# RF_old.net
KiCad netlist of a schematic drawn in Altium Designer
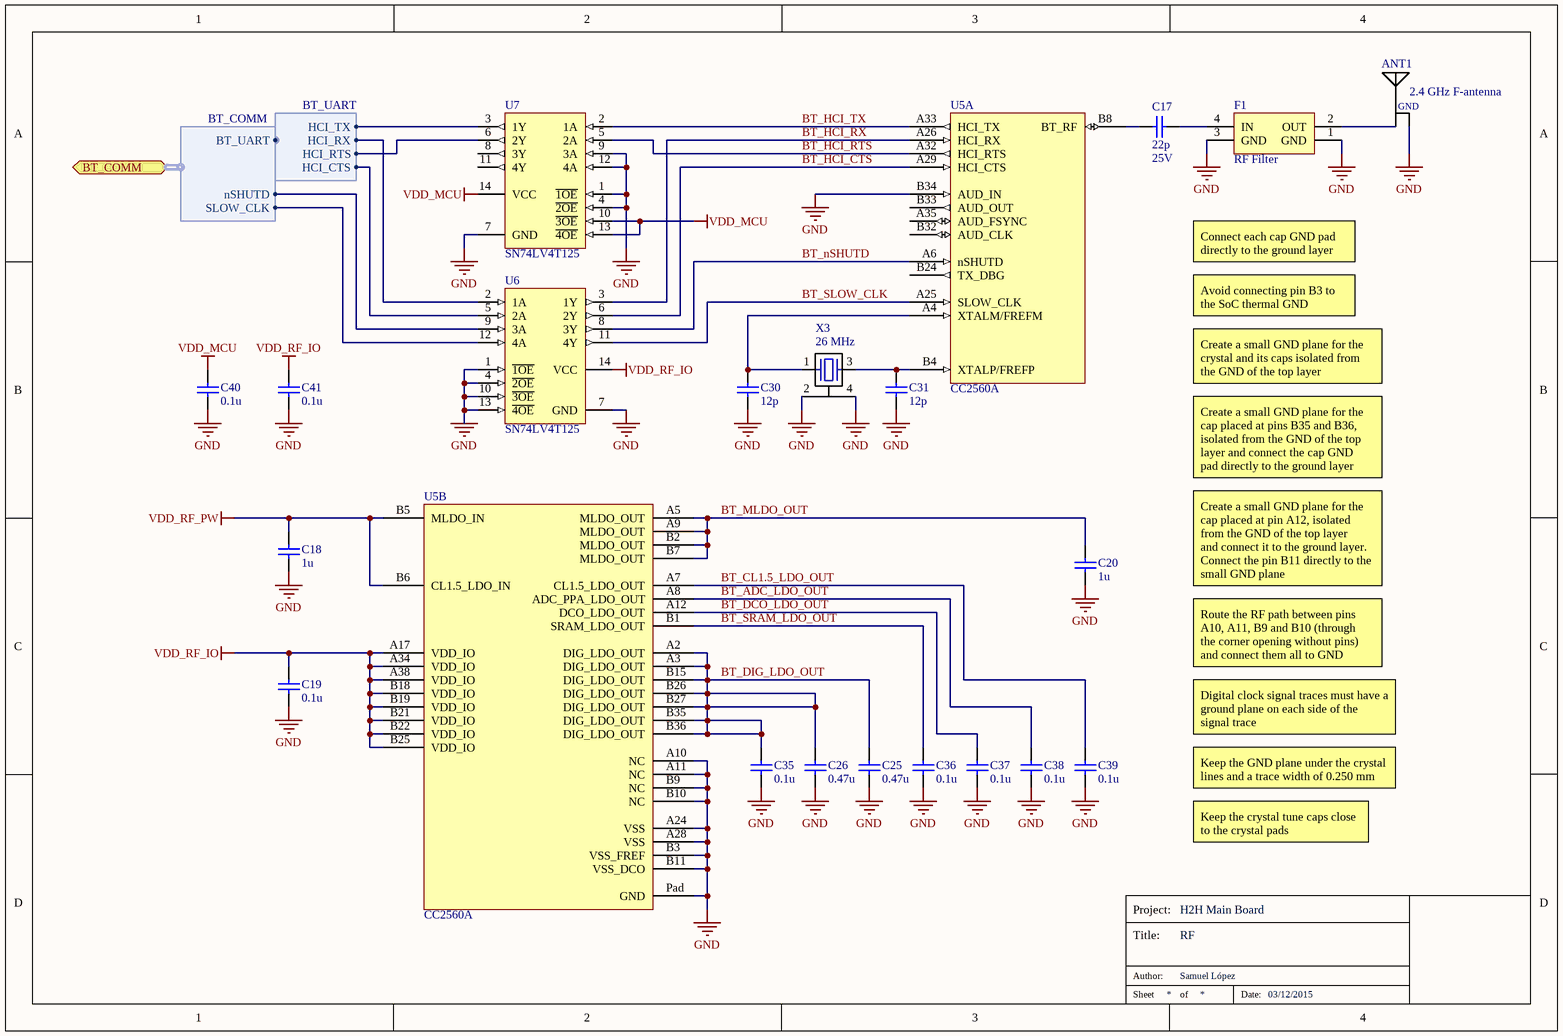
[diagram p0: RF_old.SchDoc]

(export (version "E")
  (design (tool "Eeschema 10.0.6"))
  (components
    (comp (ref "ANT1")
      (value "2.4 GHz F-antenna")
      (footprint "Antenna")
      (libsource (lib "Main Board") (part "Antenna"))
    )
    (comp (ref "C17")
      (value "22p")
      (footprint "C0603")
      (description "Capacitor")
      (fields (field (name "RATED VOLTAGE") "25V"))
      (libsource (lib "Common Devices") (part "Capacitor"))
    )
    (comp (ref "C18")
      (value "1u")
      (footprint "C0603")
      (description "Capacitor")
      (libsource (lib "Common Devices") (part "Capacitor"))
    )
    (comp (ref "C19")
      (value "0.1u")
      (footprint "C0603")
      (description "Capacitor")
      (libsource (lib "Common Devices") (part "Capacitor"))
    )
    (comp (ref "C20")
      (value "1u")
      (footprint "C0603")
      (description "Capacitor")
      (libsource (lib "Common Devices") (part "Capacitor"))
    )
    (comp (ref "C25")
      (value "0.47u")
      (footprint "C0603")
      (description "Capacitor")
      (libsource (lib "Common Devices") (part "Capacitor"))
    )
    (comp (ref "C26")
      (value "0.47u")
      (footprint "C0603")
      (description "Capacitor")
      (libsource (lib "Common Devices") (part "Capacitor"))
    )
    (comp (ref "C30")
      (value "12p")
      (footprint "C0603")
      (description "Capacitor")
      (libsource (lib "Common Devices") (part "Capacitor"))
    )
    (comp (ref "C31")
      (value "12p")
      (footprint "C0603")
      (description "Capacitor")
      (libsource (lib "Common Devices") (part "Capacitor"))
    )
    (comp (ref "C35")
      (value "0.1u")
      (footprint "C0603")
      (description "Capacitor")
      (libsource (lib "Common Devices") (part "Capacitor"))
    )
    (comp (ref "C36")
      (value "0.1u")
      (footprint "C0603")
      (description "Capacitor")
      (libsource (lib "Common Devices") (part "Capacitor"))
    )
    (comp (ref "C37")
      (value "0.1u")
      (footprint "C0603")
      (description "Capacitor")
      (libsource (lib "Common Devices") (part "Capacitor"))
    )
    (comp (ref "C38")
      (value "0.1u")
      (footprint "C0603")
      (description "Capacitor")
      (libsource (lib "Common Devices") (part "Capacitor"))
    )
    (comp (ref "C39")
      (value "0.1u")
      (footprint "C0603")
      (description "Capacitor")
      (libsource (lib "Common Devices") (part "Capacitor"))
    )
    (comp (ref "C40")
      (value "0.1u")
      (footprint "C0603")
      (description "Capacitor")
      (libsource (lib "Common Devices") (part "Capacitor"))
    )
    (comp (ref "C41")
      (value "0.1u")
      (footprint "C0603")
      (description "Capacitor")
      (libsource (lib "Common Devices") (part "Capacitor"))
    )
    (comp (ref "F1")
      (value "RF Filter")
      (footprint "LFB212G45SG8A127")
      (description "RF Filter 2.4 GHz")
      (libsource (lib "Main Board") (part "LFB212G45SG8A127"))
    )
    (comp (ref "U5")
      (value "CC2560A")
      (footprint "CC2560")
      (description "Bluetooth - BT 4.0 controller (BR/EDR)")
      (libsource (lib "Main Board") (part "CC2560A"))
    )
    (comp (ref "U6")
      (value "SN74LV4T125")
      (footprint "PQFN-14")
      (description "Level Translator")
      (libsource (lib "") (part "SN74LV4T125_1"))
    )
    (comp (ref "U7")
      (value "SN74LV4T125")
      (footprint "PQFN-14")
      (description "Level Translator")
      (libsource (lib "Main Board") (part "SN74LV4T125"))
    )
    (comp (ref "X3")
      (value "NX2016SA")
      (footprint "NX2016SA")
      (description "Crystal - 26 MHz")
      (fields (field (name "FREQUENCY") "26 MHz"))
      (libsource (lib "Main Board") (part "NX2016SA"))
    )
  )
  (nets
    (net (code "2") (name "/BT_ADC_LDO_OUT") (class "Default")
      (node (ref "C38") (pin "2") (pinfunction "2_2") (pintype "passive"))
      (node (ref "U5") (pin "A8") (pinfunction "ADC_PPA_LDO_OUT_A8") (pintype "power_in"))
    )
    (net (code "3") (name "/BT_CL1.5_LDO_OUT") (class "Default")
      (node (ref "C39") (pin "2") (pinfunction "2_2") (pintype "passive"))
      (node (ref "U5") (pin "A7") (pinfunction "CL1.5_LDO_OUT_A7") (pintype "power_in"))
    )
    (net (code "4") (name "/BT_DCO_LDO_OUT") (class "Default")
      (node (ref "C37") (pin "2") (pinfunction "2_2") (pintype "passive"))
      (node (ref "U5") (pin "A12") (pinfunction "DCO_LDO_OUT_A12") (pintype "power_in"))
    )
    (net (code "5") (name "/BT_DIG_LDO_OUT") (class "Default")
      (node (ref "C25") (pin "2") (pinfunction "2_2") (pintype "passive"))
      (node (ref "C26") (pin "2") (pinfunction "2_2") (pintype "passive"))
      (node (ref "C35") (pin "2") (pinfunction "2_2") (pintype "passive"))
      (node (ref "U5") (pin "A2") (pinfunction "DIG_LDO_OUT_A2") (pintype "power_in"))
      (node (ref "U5") (pin "A3") (pinfunction "DIG_LDO_OUT_A3") (pintype "power_in"))
      (node (ref "U5") (pin "B15") (pinfunction "DIG_LDO_OUT_B15") (pintype "power_in"))
      (node (ref "U5") (pin "B26") (pinfunction "DIG_LDO_OUT_B26") (pintype "power_in"))
      (node (ref "U5") (pin "B27") (pinfunction "DIG_LDO_OUT_B27") (pintype "power_in"))
      (node (ref "U5") (pin "B35") (pinfunction "DIG_LDO_OUT_B35") (pintype "power_in"))
      (node (ref "U5") (pin "B36") (pinfunction "DIG_LDO_OUT_B36") (pintype "power_in"))
    )
    (net (code "6") (name "/BT_HCI_CTS") (class "Default")
      (node (ref "U5") (pin "A29") (pinfunction "HCI_CTS_A29") (pintype "input"))
      (node (ref "U6") (pin "6") (pinfunction "2Y_6") (pintype "output"))
    )
    (net (code "7") (name "/BT_HCI_RTS") (class "Default")
      (node (ref "U5") (pin "A32") (pinfunction "HCI_RTS_A32") (pintype "output"))
      (node (ref "U7") (pin "5") (pinfunction "2A_5") (pintype "input"))
    )
    (net (code "8") (name "/BT_HCI_RX") (class "Default")
      (node (ref "U5") (pin "A26") (pinfunction "HCI_RX_A26") (pintype "input"))
      (node (ref "U6") (pin "3") (pinfunction "1Y_3") (pintype "output"))
    )
    (net (code "9") (name "/BT_HCI_TX") (class "Default")
      (node (ref "U5") (pin "A33") (pinfunction "HCI_TX_A33") (pintype "output"))
      (node (ref "U7") (pin "2") (pinfunction "1A_2") (pintype "input"))
    )
    (net (code "10") (name "/BT_MLDO_OUT") (class "Default")
      (node (ref "C20") (pin "2") (pinfunction "2_2") (pintype "passive"))
      (node (ref "U5") (pin "A5") (pinfunction "MLDO_OUT_A5") (pintype "power_in"))
      (node (ref "U5") (pin "A9") (pinfunction "MLDO_OUT_A9") (pintype "power_in"))
      (node (ref "U5") (pin "B2") (pinfunction "MLDO_OUT_B2") (pintype "power_in"))
      (node (ref "U5") (pin "B7") (pinfunction "MLDO_OUT_B7") (pintype "power_in"))
    )
    (net (code "11") (name "/BT_SLOW_CLK") (class "Default")
      (node (ref "U5") (pin "A25") (pinfunction "SLOW_CLK_A25") (pintype "input"))
      (node (ref "U6") (pin "11") (pinfunction "4Y_11") (pintype "output"))
    )
    (net (code "12") (name "/BT_SRAM_LDO_OUT") (class "Default")
      (node (ref "C36") (pin "2") (pinfunction "2_2") (pintype "passive"))
      (node (ref "U5") (pin "B1") (pinfunction "SRAM_LDO_OUT_B1") (pintype "power_in"))
    )
    (net (code "13") (name "/BT_nSHUTD") (class "Default")
      (node (ref "U5") (pin "A6") (pinfunction "nSHUTD_A6") (pintype "input"))
      (node (ref "U6") (pin "8") (pinfunction "3Y_8") (pintype "output"))
    )
    (net (code "14") (name "/HCI_CTS") (class "Default")
      (node (ref "U6") (pin "5") (pinfunction "2A_5") (pintype "input"))
    )
    (net (code "15") (name "/HCI_RTS") (class "Default")
      (node (ref "U7") (pin "6") (pinfunction "2Y_6") (pintype "output"))
    )
    (net (code "16") (name "/HCI_RX") (class "Default")
      (node (ref "U6") (pin "2") (pinfunction "1A_2") (pintype "input"))
    )
    (net (code "17") (name "/HCI_TX") (class "Default")
      (node (ref "U7") (pin "3") (pinfunction "1Y_3") (pintype "output"))
    )
    (net (code "18") (name "/SLOW_CLK") (class "Default")
      (node (ref "U6") (pin "12") (pinfunction "4A_12") (pintype "input"))
    )
    (net (code "19") (name "/nSHUTD") (class "Default")
      (node (ref "U6") (pin "9") (pinfunction "3A_9") (pintype "input"))
    )
    (net (code "21") (name "GND") (class "Default")
      (node (ref "ANT1") (pin "2") (pinfunction "GND_2") (pintype "passive"))
      (node (ref "C18") (pin "1") (pinfunction "1_1") (pintype "passive"))
      (node (ref "C19") (pin "1") (pinfunction "1_1") (pintype "passive"))
      (node (ref "C20") (pin "1") (pinfunction "1_1") (pintype "passive"))
      (node (ref "C25") (pin "1") (pinfunction "1_1") (pintype "passive"))
      (node (ref "C26") (pin "1") (pinfunction "1_1") (pintype "passive"))
      (node (ref "C30") (pin "2") (pinfunction "2_2") (pintype "passive"))
      (node (ref "C31") (pin "2") (pinfunction "2_2") (pintype "passive"))
      (node (ref "C35") (pin "1") (pinfunction "1_1") (pintype "passive"))
      (node (ref "C36") (pin "1") (pinfunction "1_1") (pintype "passive"))
      (node (ref "C37") (pin "1") (pinfunction "1_1") (pintype "passive"))
      (node (ref "C38") (pin "1") (pinfunction "1_1") (pintype "passive"))
      (node (ref "C39") (pin "1") (pinfunction "1_1") (pintype "passive"))
      (node (ref "C40") (pin "1") (pinfunction "1_1") (pintype "passive"))
      (node (ref "C41") (pin "1") (pinfunction "1_1") (pintype "passive"))
      (node (ref "F1") (pin "1") (pinfunction "GND_1") (pintype "power_in"))
      (node (ref "F1") (pin "3") (pinfunction "GND_3") (pintype "power_in"))
      (node (ref "U5") (pin "A10") (pinfunction "NC_A10") (pintype "passive"))
      (node (ref "U5") (pin "A11") (pinfunction "NC_A11") (pintype "passive"))
      (node (ref "U5") (pin "A24") (pinfunction "VSS_A24") (pintype "power_in"))
      (node (ref "U5") (pin "A28") (pinfunction "VSS_A28") (pintype "power_in"))
      (node (ref "U5") (pin "B10") (pinfunction "NC_B10") (pintype "passive"))
      (node (ref "U5") (pin "B11") (pinfunction "VSS_DCO_B11") (pintype "power_in"))
      (node (ref "U5") (pin "B3") (pinfunction "VSS_FREF_B3") (pintype "power_in"))
      (node (ref "U5") (pin "B34") (pinfunction "AUD_IN_B34") (pintype "input"))
      (node (ref "U5") (pin "B9") (pinfunction "NC_B9") (pintype "passive"))
      (node (ref "U5") (pin "Pad") (pinfunction "GND_Pad") (pintype "power_in"))
      (node (ref "U6") (pin "1") (pinfunction "~{1OE}_1") (pintype "input"))
      (node (ref "U6") (pin "10") (pinfunction "~{3OE}_10") (pintype "input"))
      (node (ref "U6") (pin "13") (pinfunction "~{4OE}_13") (pintype "input"))
      (node (ref "U6") (pin "4") (pinfunction "~{2OE}_4") (pintype "input"))
      (node (ref "U6") (pin "7") (pinfunction "GND_7") (pintype "power_in"))
      (node (ref "U7") (pin "1") (pinfunction "~{1OE}_1") (pintype "input"))
      (node (ref "U7") (pin "12") (pinfunction "4A_12") (pintype "input"))
      (node (ref "U7") (pin "4") (pinfunction "~{2OE}_4") (pintype "input"))
      (node (ref "U7") (pin "7") (pinfunction "GND_7") (pintype "power_in"))
      (node (ref "U7") (pin "9") (pinfunction "3A_9") (pintype "input"))
      (node (ref "X3") (pin "2") (pinfunction "2_2") (pintype "passive"))
      (node (ref "X3") (pin "4") (pinfunction "4_4") (pintype "passive"))
    )
    (net (code "22") (name "Net-(ANT1-IN)") (class "Default")
      (node (ref "ANT1") (pin "1") (pinfunction "IN_1") (pintype "passive"))
      (node (ref "F1") (pin "2") (pinfunction "OUT_2") (pintype "passive"))
    )
    (net (code "23") (name "Net-(F1-IN)") (class "Default")
      (node (ref "C17") (pin "1") (pinfunction "1_1") (pintype "passive"))
      (node (ref "F1") (pin "4") (pinfunction "IN_4") (pintype "power_in"))
    )
    (net (code "24") (name "Net-(U5A-BT_RF)") (class "Default")
      (node (ref "C17") (pin "2") (pinfunction "2_2") (pintype "passive"))
      (node (ref "U5") (pin "B8") (pinfunction "BT_RF_B8") (pintype "bidirectional"))
    )
    (net (code "25") (name "Net-(U5A-XTALM{slash}FREFM)") (class "Default")
      (node (ref "C30") (pin "1") (pinfunction "1_1") (pintype "passive"))
      (node (ref "U5") (pin "A4") (pinfunction "XTALM/FREFM_A4") (pintype "input"))
      (node (ref "X3") (pin "1") (pinfunction "1_1") (pintype "passive"))
    )
    (net (code "26") (name "Net-(U5A-XTALP{slash}FREFP)") (class "Default")
      (node (ref "C31") (pin "1") (pinfunction "1_1") (pintype "passive"))
      (node (ref "U5") (pin "B4") (pinfunction "XTALP/FREFP_B4") (pintype "input"))
      (node (ref "X3") (pin "3") (pinfunction "3_3") (pintype "passive"))
    )
    (net (code "27") (name "VDD_MCU") (class "Default")
      (node (ref "C40") (pin "2") (pinfunction "2_2") (pintype "passive"))
      (node (ref "U7") (pin "10") (pinfunction "~{3OE}_10") (pintype "input"))
      (node (ref "U7") (pin "13") (pinfunction "~{4OE}_13") (pintype "input"))
      (node (ref "U7") (pin "14") (pinfunction "VCC_14") (pintype "power_in"))
    )
    (net (code "28") (name "VDD_RF_IO") (class "Default")
      (node (ref "C19") (pin "2") (pinfunction "2_2") (pintype "passive"))
      (node (ref "C41") (pin "2") (pinfunction "2_2") (pintype "passive"))
      (node (ref "U5") (pin "A17") (pinfunction "VDD_IO_A17") (pintype "power_in"))
      (node (ref "U5") (pin "A34") (pinfunction "VDD_IO_A34") (pintype "power_in"))
      (node (ref "U5") (pin "A38") (pinfunction "VDD_IO_A38") (pintype "power_in"))
      (node (ref "U5") (pin "B18") (pinfunction "VDD_IO_B18") (pintype "power_in"))
      (node (ref "U5") (pin "B19") (pinfunction "VDD_IO_B19") (pintype "power_in"))
      (node (ref "U5") (pin "B21") (pinfunction "VDD_IO_B21") (pintype "power_in"))
      (node (ref "U5") (pin "B22") (pinfunction "VDD_IO_B22") (pintype "power_in"))
      (node (ref "U5") (pin "B25") (pinfunction "VDD_IO_B25") (pintype "power_in"))
      (node (ref "U6") (pin "14") (pinfunction "VCC_14") (pintype "power_in"))
    )
    (net (code "29") (name "VDD_RF_PW") (class "Default")
      (node (ref "C18") (pin "2") (pinfunction "2_2") (pintype "passive"))
      (node (ref "U5") (pin "B5") (pinfunction "MLDO_IN_B5") (pintype "power_in"))
      (node (ref "U5") (pin "B6") (pinfunction "CL1.5_LDO_IN_B6") (pintype "power_in"))
    )
    (net (code "30") (name "unconnected-(U5A-AUD_CLK-PadB32)") (class "Default")
      (node (ref "U5") (pin "B32") (pinfunction "AUD_CLK_B32") (pintype "bidirectional"))
    )
    (net (code "31") (name "unconnected-(U5A-AUD_FSYNC-PadA35)") (class "Default")
      (node (ref "U5") (pin "A35") (pinfunction "AUD_FSYNC_A35") (pintype "bidirectional"))
    )
    (net (code "32") (name "unconnected-(U5A-AUD_OUT-PadB33)") (class "Default")
      (node (ref "U5") (pin "B33") (pinfunction "AUD_OUT_B33") (pintype "output"))
    )
    (net (code "33") (name "unconnected-(U5A-TX_DBG-PadB24)") (class "Default")
      (node (ref "U5") (pin "B24") (pinfunction "TX_DBG_B24") (pintype "output"))
    )
    (net (code "34") (name "unconnected-(U7-3Y-Pad8)") (class "Default")
      (node (ref "U7") (pin "8") (pinfunction "3Y_8") (pintype "output"))
    )
    (net (code "35") (name "unconnected-(U7-4Y-Pad11)") (class "Default")
      (node (ref "U7") (pin "11") (pinfunction "4Y_11") (pintype "output"))
    )
  )
)
